# SOIC8_breakout.net
KiCad netlist of a schematic drawn in Altium Designer
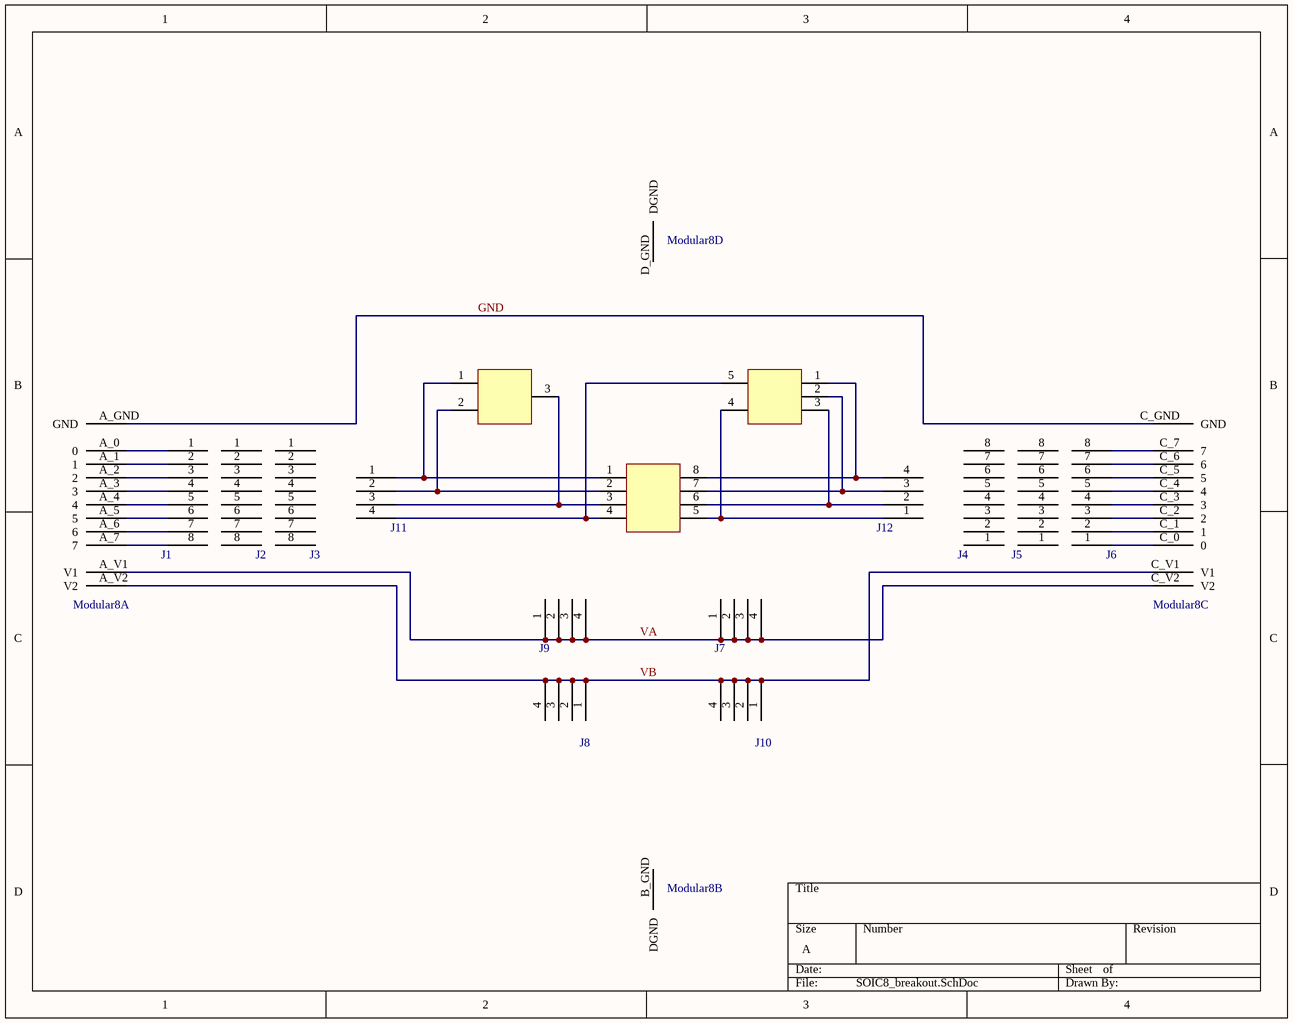
[diagram p0: SOIC8_breakout.SchDoc]

(export (version "E")
  (design (tool "Eeschema 10.0.6"))
  (components
    (comp (ref "J1")
      (value "8x1")
      (footprint "8x1 THRU HOLES 0.1\" PITCH")
      (libsource (lib "OpBots") (part "8x1"))
    )
    (comp (ref "J2")
      (value "8x1")
      (footprint "8x1 THRU HOLES 0.1\" PITCH")
      (libsource (lib "OpBots") (part "8x1"))
    )
    (comp (ref "J3")
      (value "8x1")
      (footprint "8x1 THRU HOLES 0.1\" PITCH")
      (libsource (lib "OpBots") (part "8x1"))
    )
    (comp (ref "J4")
      (value "8x1")
      (footprint "8x1 THRU HOLES 0.1\" PITCH")
      (libsource (lib "OpBots") (part "8x1"))
    )
    (comp (ref "J5")
      (value "8x1")
      (footprint "8x1 THRU HOLES 0.1\" PITCH")
      (libsource (lib "OpBots") (part "8x1"))
    )
    (comp (ref "J6")
      (value "8x1")
      (footprint "8x1 THRU HOLES 0.1\" PITCH")
      (libsource (lib "OpBots") (part "8x1"))
    )
    (comp (ref "J7")
      (value "4x1")
      (footprint "4x1 THRU HOLES 0.1\" PITCH")
      (libsource (lib "OpBots") (part "4x1"))
    )
    (comp (ref "J8")
      (value "4x1")
      (footprint "4x1 THRU HOLES 0.1\" PITCH")
      (libsource (lib "OpBots") (part "4x1"))
    )
    (comp (ref "J9")
      (value "4x1")
      (footprint "4x1 THRU HOLES 0.1\" PITCH")
      (libsource (lib "OpBots") (part "4x1"))
    )
    (comp (ref "J10")
      (value "4x1")
      (footprint "4x1 THRU HOLES 0.1\" PITCH")
      (libsource (lib "OpBots") (part "4x1"))
    )
    (comp (ref "J11")
      (value "4x1")
      (footprint "4x1 THRU HOLES 0.1\" PITCH")
      (libsource (lib "OpBots") (part "4x1"))
    )
    (comp (ref "J12")
      (value "4x1")
      (footprint "4x1 THRU HOLES 0.1\" PITCH")
      (libsource (lib "OpBots") (part "4x1"))
    )
    (comp (ref "Modular8")
      (value "modular8_rev2_A&C")
      (footprint "modular8 edges A & C")
      (libsource (lib "OpBots") (part "modular8_rev2_A&C"))
    )
    (comp (ref "S1")
      (value "Generic 8-pin device")
      (footprint "SOIC8")
      (libsource (lib "OpBots") (part "Generic 8-pin device"))
    )
    (comp (ref "S2")
      (value "Generic 3-pin device")
      (footprint "SOT-23-3")
      (libsource (lib "OpBots") (part "Generic 3-pin device"))
    )
    (comp (ref "S3")
      (value "Generic 5-pin device")
      (footprint "SOT-23-5")
      (libsource (lib "OpBots") (part "Generic 5-pin device"))
    )
  )
  (nets
    (net (code "1") (name "/GND") (class "Default")
      (node (ref "Modular8") (pin "A_GND") (pinfunction "GND_A_GND") (pintype "passive"))
      (node (ref "Modular8") (pin "C_GND") (pinfunction "GND_C_GND") (pintype "passive"))
    )
    (net (code "2") (name "/VA") (class "Default")
      (node (ref "J7") (pin "1") (pintype "passive"))
      (node (ref "J7") (pin "2") (pintype "passive"))
      (node (ref "J7") (pin "3") (pintype "passive"))
      (node (ref "J7") (pin "4") (pintype "passive"))
      (node (ref "J9") (pin "1") (pintype "passive"))
      (node (ref "J9") (pin "2") (pintype "passive"))
      (node (ref "J9") (pin "3") (pintype "passive"))
      (node (ref "J9") (pin "4") (pintype "passive"))
      (node (ref "Modular8") (pin "A_V1") (pinfunction "V1_A_V1") (pintype "passive"))
      (node (ref "Modular8") (pin "C_V2") (pinfunction "V2_C_V2") (pintype "passive"))
    )
    (net (code "3") (name "/VB") (class "Default")
      (node (ref "J10") (pin "1") (pintype "passive"))
      (node (ref "J10") (pin "2") (pintype "passive"))
      (node (ref "J10") (pin "3") (pintype "passive"))
      (node (ref "J10") (pin "4") (pintype "passive"))
      (node (ref "J8") (pin "1") (pintype "passive"))
      (node (ref "J8") (pin "2") (pintype "passive"))
      (node (ref "J8") (pin "3") (pintype "passive"))
      (node (ref "J8") (pin "4") (pintype "passive"))
      (node (ref "Modular8") (pin "A_V2") (pinfunction "V2_A_V2") (pintype "passive"))
      (node (ref "Modular8") (pin "C_V1") (pinfunction "V1_C_V1") (pintype "passive"))
    )
    (net (code "4") (name "Net-(J11-Pad1)") (class "Default")
      (node (ref "J11") (pin "1") (pintype "passive"))
      (node (ref "S1") (pin "1") (pinfunction "1_1") (pintype "passive"))
      (node (ref "S2") (pin "1") (pinfunction "1_1") (pintype "passive"))
    )
    (net (code "5") (name "Net-(J11-Pad2)") (class "Default")
      (node (ref "J11") (pin "2") (pintype "passive"))
      (node (ref "S1") (pin "2") (pinfunction "2_2") (pintype "passive"))
      (node (ref "S2") (pin "2") (pinfunction "2_2") (pintype "passive"))
    )
    (net (code "6") (name "Net-(J11-Pad3)") (class "Default")
      (node (ref "J11") (pin "3") (pintype "passive"))
      (node (ref "S1") (pin "3") (pinfunction "3_3") (pintype "passive"))
      (node (ref "S2") (pin "3") (pinfunction "3_3") (pintype "passive"))
    )
    (net (code "7") (name "Net-(J11-Pad4)") (class "Default")
      (node (ref "J11") (pin "4") (pintype "passive"))
      (node (ref "S1") (pin "4") (pinfunction "4_4") (pintype "passive"))
      (node (ref "S3") (pin "5") (pinfunction "5_5") (pintype "passive"))
    )
    (net (code "8") (name "Net-(J12-Pad1)") (class "Default")
      (node (ref "J12") (pin "1") (pintype "passive"))
      (node (ref "S1") (pin "5") (pinfunction "5_5") (pintype "passive"))
      (node (ref "S3") (pin "4") (pinfunction "4_4") (pintype "passive"))
    )
    (net (code "9") (name "Net-(J12-Pad2)") (class "Default")
      (node (ref "J12") (pin "2") (pintype "passive"))
      (node (ref "S1") (pin "6") (pinfunction "6_6") (pintype "passive"))
      (node (ref "S3") (pin "3") (pinfunction "3_3") (pintype "passive"))
    )
    (net (code "10") (name "Net-(J12-Pad3)") (class "Default")
      (node (ref "J12") (pin "3") (pintype "passive"))
      (node (ref "S1") (pin "7") (pinfunction "7_7") (pintype "passive"))
      (node (ref "S3") (pin "2") (pinfunction "2_2") (pintype "passive"))
    )
    (net (code "11") (name "Net-(J12-Pad4)") (class "Default")
      (node (ref "J12") (pin "4") (pintype "passive"))
      (node (ref "S1") (pin "8") (pinfunction "8_8") (pintype "passive"))
      (node (ref "S3") (pin "1") (pinfunction "1_1") (pintype "passive"))
    )
    (net (code "12") (name "Net-(Modular8A-0)") (class "Default")
      (node (ref "J1") (pin "1") (pintype "passive"))
      (node (ref "Modular8") (pin "A_0") (pinfunction "0_A_0") (pintype "passive"))
    )
    (net (code "13") (name "Net-(Modular8A-1)") (class "Default")
      (node (ref "J1") (pin "2") (pintype "passive"))
      (node (ref "Modular8") (pin "A_1") (pinfunction "1_A_1") (pintype "passive"))
    )
    (net (code "14") (name "Net-(Modular8A-2)") (class "Default")
      (node (ref "J1") (pin "3") (pintype "passive"))
      (node (ref "Modular8") (pin "A_2") (pinfunction "2_A_2") (pintype "passive"))
    )
    (net (code "15") (name "Net-(Modular8A-3)") (class "Default")
      (node (ref "J1") (pin "4") (pintype "passive"))
      (node (ref "Modular8") (pin "A_3") (pinfunction "3_A_3") (pintype "passive"))
    )
    (net (code "16") (name "Net-(Modular8A-4)") (class "Default")
      (node (ref "J1") (pin "5") (pintype "passive"))
      (node (ref "Modular8") (pin "A_4") (pinfunction "4_A_4") (pintype "passive"))
    )
    (net (code "17") (name "Net-(Modular8A-5)") (class "Default")
      (node (ref "J1") (pin "6") (pintype "passive"))
      (node (ref "Modular8") (pin "A_5") (pinfunction "5_A_5") (pintype "passive"))
    )
    (net (code "18") (name "Net-(Modular8A-6)") (class "Default")
      (node (ref "J1") (pin "7") (pintype "passive"))
      (node (ref "Modular8") (pin "A_6") (pinfunction "6_A_6") (pintype "passive"))
    )
    (net (code "19") (name "Net-(Modular8A-7)") (class "Default")
      (node (ref "J1") (pin "8") (pintype "passive"))
      (node (ref "Modular8") (pin "A_7") (pinfunction "7_A_7") (pintype "passive"))
    )
    (net (code "20") (name "Net-(Modular8C-0)") (class "Default")
      (node (ref "J6") (pin "1") (pintype "passive"))
      (node (ref "Modular8") (pin "C_0") (pinfunction "0_C_0") (pintype "passive"))
    )
    (net (code "21") (name "Net-(Modular8C-1)") (class "Default")
      (node (ref "J6") (pin "2") (pintype "passive"))
      (node (ref "Modular8") (pin "C_1") (pinfunction "1_C_1") (pintype "passive"))
    )
    (net (code "22") (name "Net-(Modular8C-2)") (class "Default")
      (node (ref "J6") (pin "3") (pintype "passive"))
      (node (ref "Modular8") (pin "C_2") (pinfunction "2_C_2") (pintype "passive"))
    )
    (net (code "23") (name "Net-(Modular8C-3)") (class "Default")
      (node (ref "J6") (pin "4") (pintype "passive"))
      (node (ref "Modular8") (pin "C_3") (pinfunction "3_C_3") (pintype "passive"))
    )
    (net (code "24") (name "Net-(Modular8C-4)") (class "Default")
      (node (ref "J6") (pin "5") (pintype "passive"))
      (node (ref "Modular8") (pin "C_4") (pinfunction "4_C_4") (pintype "passive"))
    )
    (net (code "25") (name "Net-(Modular8C-5)") (class "Default")
      (node (ref "J6") (pin "6") (pintype "passive"))
      (node (ref "Modular8") (pin "C_5") (pinfunction "5_C_5") (pintype "passive"))
    )
    (net (code "26") (name "Net-(Modular8C-6)") (class "Default")
      (node (ref "J6") (pin "7") (pintype "passive"))
      (node (ref "Modular8") (pin "C_6") (pinfunction "6_C_6") (pintype "passive"))
    )
    (net (code "27") (name "Net-(Modular8C-7)") (class "Default")
      (node (ref "J6") (pin "8") (pintype "passive"))
      (node (ref "Modular8") (pin "C_7") (pinfunction "7_C_7") (pintype "passive"))
    )
    (net (code "28") (name "unconnected-(J2-Pad1)") (class "Default")
      (node (ref "J2") (pin "1") (pintype "passive"))
    )
    (net (code "29") (name "unconnected-(J2-Pad2)") (class "Default")
      (node (ref "J2") (pin "2") (pintype "passive"))
    )
    (net (code "30") (name "unconnected-(J2-Pad3)") (class "Default")
      (node (ref "J2") (pin "3") (pintype "passive"))
    )
    (net (code "31") (name "unconnected-(J2-Pad4)") (class "Default")
      (node (ref "J2") (pin "4") (pintype "passive"))
    )
    (net (code "32") (name "unconnected-(J2-Pad5)") (class "Default")
      (node (ref "J2") (pin "5") (pintype "passive"))
    )
    (net (code "33") (name "unconnected-(J2-Pad6)") (class "Default")
      (node (ref "J2") (pin "6") (pintype "passive"))
    )
    (net (code "34") (name "unconnected-(J2-Pad7)") (class "Default")
      (node (ref "J2") (pin "7") (pintype "passive"))
    )
    (net (code "35") (name "unconnected-(J2-Pad8)") (class "Default")
      (node (ref "J2") (pin "8") (pintype "passive"))
    )
    (net (code "36") (name "unconnected-(J3-Pad1)") (class "Default")
      (node (ref "J3") (pin "1") (pintype "passive"))
    )
    (net (code "37") (name "unconnected-(J3-Pad2)") (class "Default")
      (node (ref "J3") (pin "2") (pintype "passive"))
    )
    (net (code "38") (name "unconnected-(J3-Pad3)") (class "Default")
      (node (ref "J3") (pin "3") (pintype "passive"))
    )
    (net (code "39") (name "unconnected-(J3-Pad4)") (class "Default")
      (node (ref "J3") (pin "4") (pintype "passive"))
    )
    (net (code "40") (name "unconnected-(J3-Pad5)") (class "Default")
      (node (ref "J3") (pin "5") (pintype "passive"))
    )
    (net (code "41") (name "unconnected-(J3-Pad6)") (class "Default")
      (node (ref "J3") (pin "6") (pintype "passive"))
    )
    (net (code "42") (name "unconnected-(J3-Pad7)") (class "Default")
      (node (ref "J3") (pin "7") (pintype "passive"))
    )
    (net (code "43") (name "unconnected-(J3-Pad8)") (class "Default")
      (node (ref "J3") (pin "8") (pintype "passive"))
    )
    (net (code "44") (name "unconnected-(J4-Pad1)") (class "Default")
      (node (ref "J4") (pin "1") (pintype "passive"))
    )
    (net (code "45") (name "unconnected-(J4-Pad2)") (class "Default")
      (node (ref "J4") (pin "2") (pintype "passive"))
    )
    (net (code "46") (name "unconnected-(J4-Pad3)") (class "Default")
      (node (ref "J4") (pin "3") (pintype "passive"))
    )
    (net (code "47") (name "unconnected-(J4-Pad4)") (class "Default")
      (node (ref "J4") (pin "4") (pintype "passive"))
    )
    (net (code "48") (name "unconnected-(J4-Pad5)") (class "Default")
      (node (ref "J4") (pin "5") (pintype "passive"))
    )
    (net (code "49") (name "unconnected-(J4-Pad6)") (class "Default")
      (node (ref "J4") (pin "6") (pintype "passive"))
    )
    (net (code "50") (name "unconnected-(J4-Pad7)") (class "Default")
      (node (ref "J4") (pin "7") (pintype "passive"))
    )
    (net (code "51") (name "unconnected-(J4-Pad8)") (class "Default")
      (node (ref "J4") (pin "8") (pintype "passive"))
    )
    (net (code "52") (name "unconnected-(J5-Pad1)") (class "Default")
      (node (ref "J5") (pin "1") (pintype "passive"))
    )
    (net (code "53") (name "unconnected-(J5-Pad2)") (class "Default")
      (node (ref "J5") (pin "2") (pintype "passive"))
    )
    (net (code "54") (name "unconnected-(J5-Pad3)") (class "Default")
      (node (ref "J5") (pin "3") (pintype "passive"))
    )
    (net (code "55") (name "unconnected-(J5-Pad4)") (class "Default")
      (node (ref "J5") (pin "4") (pintype "passive"))
    )
    (net (code "56") (name "unconnected-(J5-Pad5)") (class "Default")
      (node (ref "J5") (pin "5") (pintype "passive"))
    )
    (net (code "57") (name "unconnected-(J5-Pad6)") (class "Default")
      (node (ref "J5") (pin "6") (pintype "passive"))
    )
    (net (code "58") (name "unconnected-(J5-Pad7)") (class "Default")
      (node (ref "J5") (pin "7") (pintype "passive"))
    )
    (net (code "59") (name "unconnected-(J5-Pad8)") (class "Default")
      (node (ref "J5") (pin "8") (pintype "passive"))
    )
    (net (code "60") (name "unconnected-(Modular8B-DGND-PadB_GND)") (class "Default")
      (node (ref "Modular8") (pin "B_GND") (pinfunction "DGND_B_GND") (pintype "passive"))
    )
    (net (code "61") (name "unconnected-(Modular8D-DGND-PadD_GND)") (class "Default")
      (node (ref "Modular8") (pin "D_GND") (pinfunction "DGND_D_GND") (pintype "passive"))
    )
  )
)
